# tvc-soundmagic-v1_3.net
KiCad netlist of a schematic drawn in EAGLE
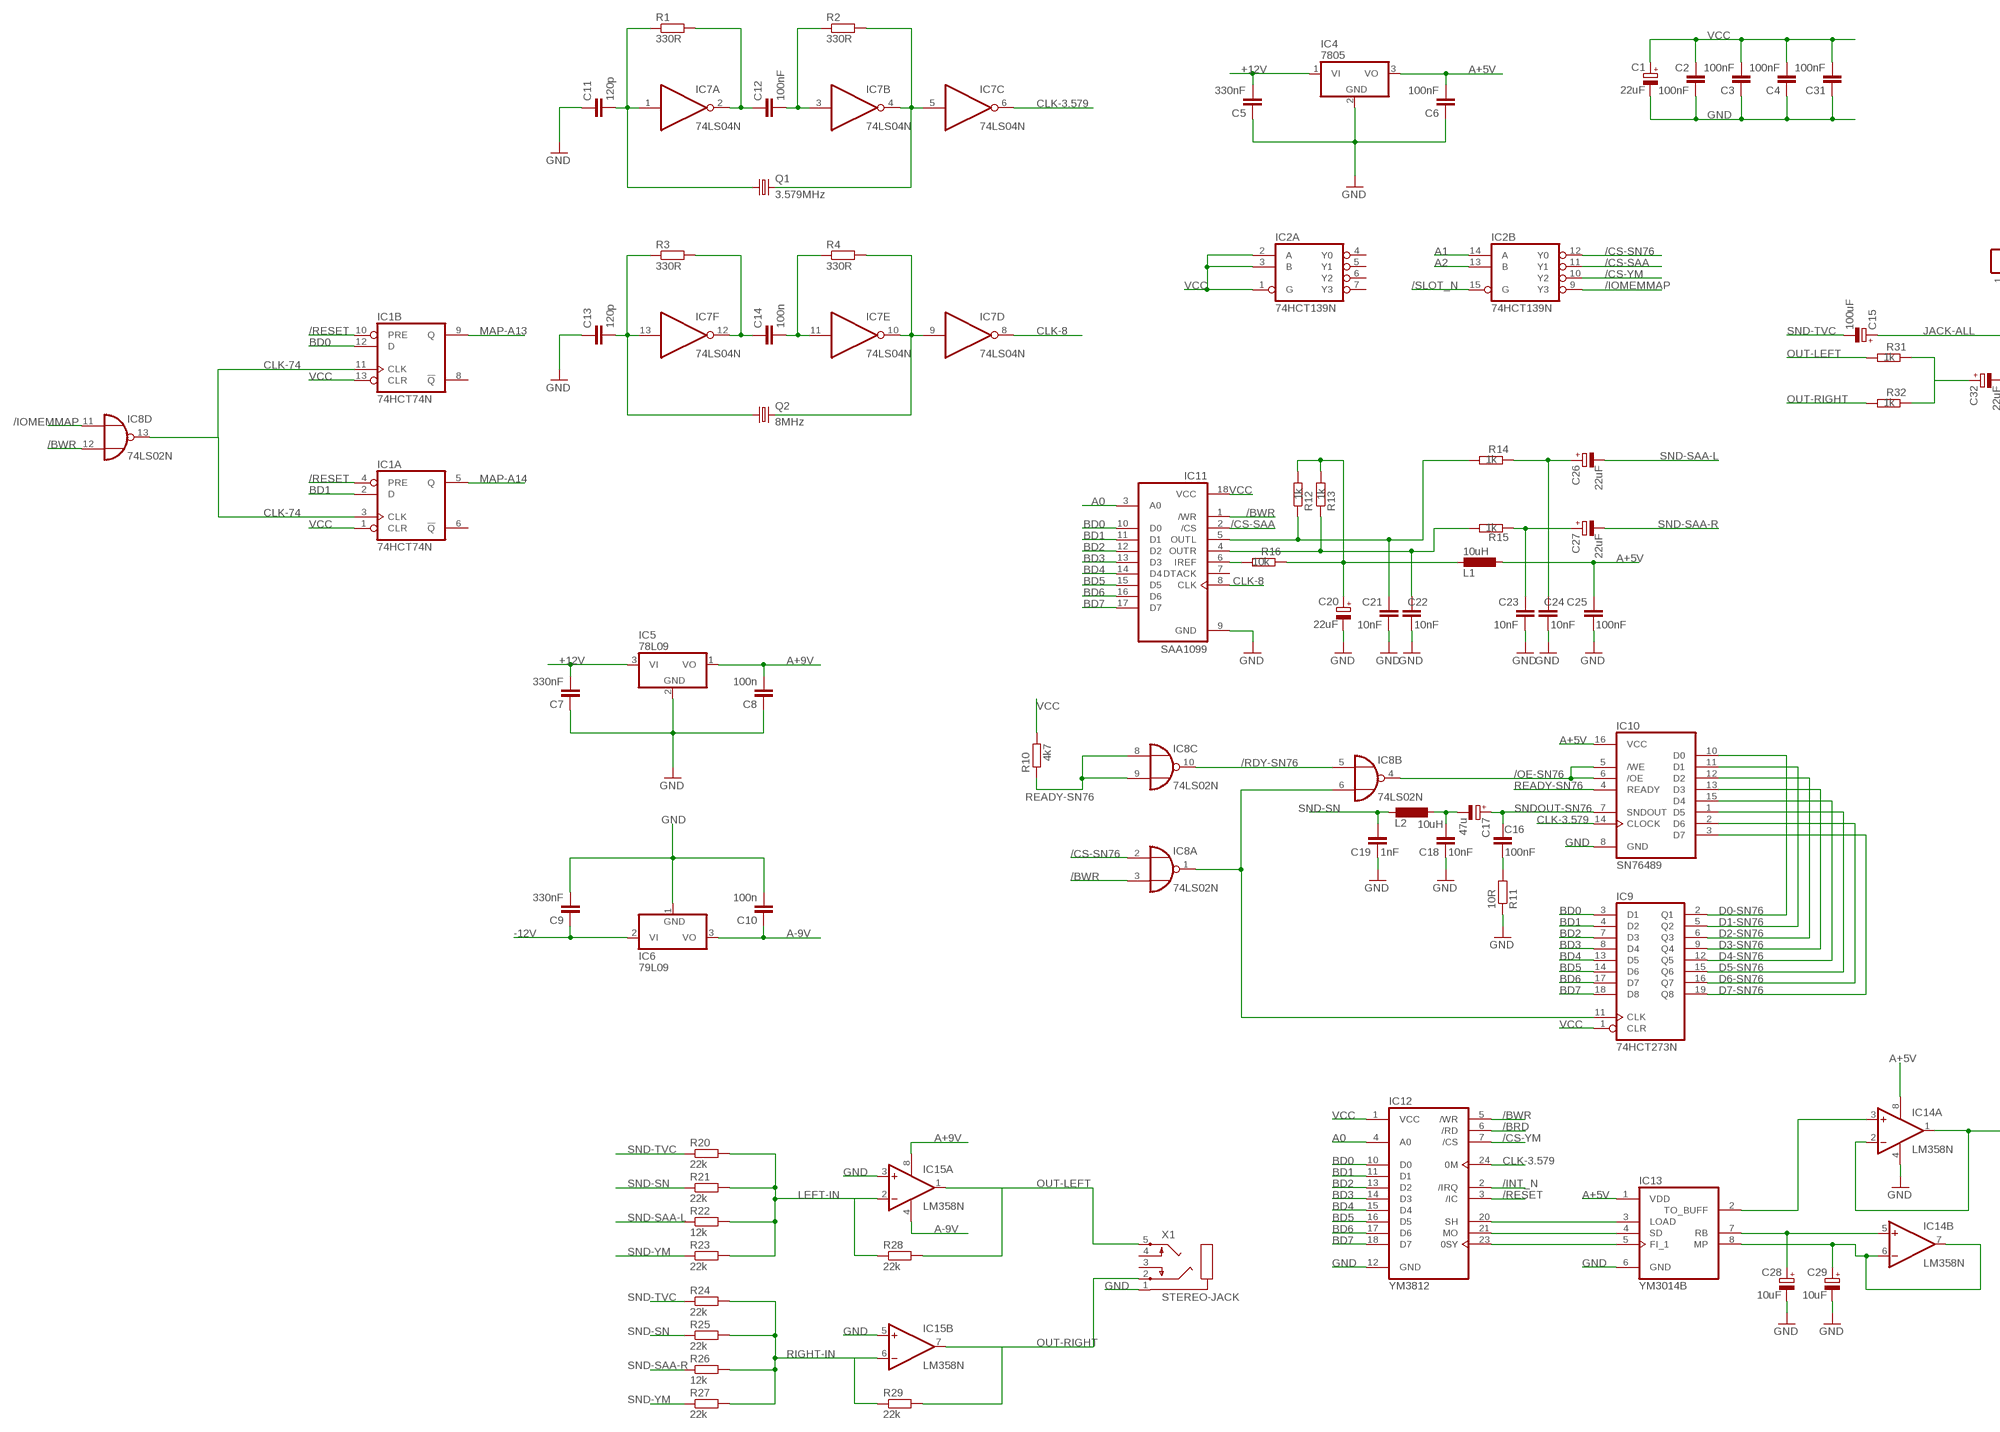
[diagram p0: schematic, sheet 1, part 1 of 2]
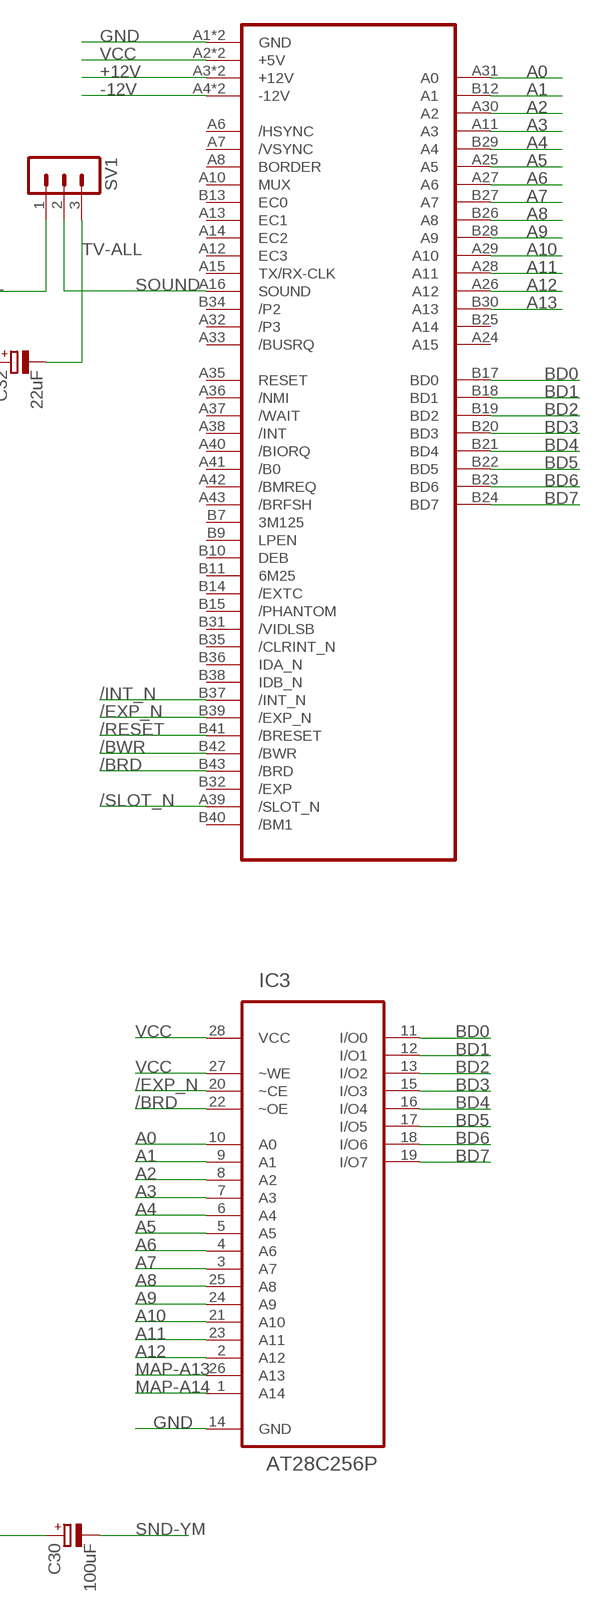
[diagram p1: schematic, sheet 1, part 2 of 2]

(export (version "E")
  (design (tool "Eeschema 10.0.6"))
  (components
    (comp (ref "C1")
      (value "22uF")
      (footprint "eagle-import:E2,5-5")
      (libsource (lib "eagle-import") (part "CPOL-EUE2.5-5"))
    )
    (comp (ref "C2")
      (value "100nF")
      (footprint "eagle-import:C2.5-2")
      (libsource (lib "eagle-import") (part "C2.5/2"))
    )
    (comp (ref "C3")
      (value "100nF")
      (footprint "eagle-import:C025-024X044")
      (libsource (lib "eagle-import") (part "C-EU025-024X044"))
    )
    (comp (ref "C4")
      (value "100nF")
      (footprint "eagle-import:C025-024X044")
      (libsource (lib "eagle-import") (part "C-EU025-024X044"))
    )
    (comp (ref "C5")
      (value "330nF")
      (footprint "eagle-import:C050-025X075")
      (libsource (lib "eagle-import") (part "C-EU050-025X075"))
    )
    (comp (ref "C6")
      (value "100nF")
      (footprint "eagle-import:C025-024X044")
      (libsource (lib "eagle-import") (part "C-EU025-024X044"))
    )
    (comp (ref "C7")
      (value "330nF")
      (footprint "eagle-import:C050-025X075")
      (libsource (lib "eagle-import") (part "C-EU050-025X075"))
    )
    (comp (ref "C8")
      (value "100n")
      (footprint "eagle-import:C025-024X044")
      (libsource (lib "eagle-import") (part "C-EU025-024X044"))
    )
    (comp (ref "C9")
      (value "330nF")
      (footprint "eagle-import:C050-025X075")
      (libsource (lib "eagle-import") (part "C-EU050-025X075"))
    )
    (comp (ref "C10")
      (value "100n")
      (footprint "eagle-import:C025-024X044")
      (libsource (lib "eagle-import") (part "C-EU025-024X044"))
    )
    (comp (ref "C11")
      (value "120p")
      (footprint "eagle-import:C025-024X044")
      (libsource (lib "eagle-import") (part "C-EU025-024X044"))
    )
    (comp (ref "C12")
      (value "100nF")
      (footprint "eagle-import:C025-024X044")
      (libsource (lib "eagle-import") (part "C-EU025-024X044"))
    )
    (comp (ref "C13")
      (value "120p")
      (footprint "eagle-import:C025-024X044")
      (libsource (lib "eagle-import") (part "C-EU025-024X044"))
    )
    (comp (ref "C14")
      (value "100n")
      (footprint "eagle-import:C025-024X044")
      (libsource (lib "eagle-import") (part "C-EU025-024X044"))
    )
    (comp (ref "C15")
      (value "100uF")
      (footprint "eagle-import:E2,5-5")
      (libsource (lib "eagle-import") (part "CPOL-EUE2.5-5"))
    )
    (comp (ref "C16")
      (value "100nF")
      (footprint "eagle-import:C2.5-2")
      (libsource (lib "eagle-import") (part "C2.5/2"))
    )
    (comp (ref "C17")
      (value "47u")
      (footprint "eagle-import:E2,5-6")
      (libsource (lib "eagle-import") (part "resistor_348_CPOL-EUE2.5-6"))
    )
    (comp (ref "C18")
      (value "10nF")
      (footprint "eagle-import:C2.5-2")
      (libsource (lib "eagle-import") (part "C2.5/2"))
    )
    (comp (ref "C19")
      (value "1nF")
      (footprint "eagle-import:C2.5-2")
      (libsource (lib "eagle-import") (part "C2.5/2"))
    )
    (comp (ref "C20")
      (value "22uF")
      (footprint "eagle-import:E2,5-5")
      (libsource (lib "eagle-import") (part "CPOL-EUE2.5-5"))
    )
    (comp (ref "C21")
      (value "10nF")
      (footprint "eagle-import:C2.5-2")
      (libsource (lib "eagle-import") (part "C2.5/2"))
    )
    (comp (ref "C22")
      (value "10nF")
      (footprint "eagle-import:C2.5-2")
      (libsource (lib "eagle-import") (part "C2.5/2"))
    )
    (comp (ref "C23")
      (value "10nF")
      (footprint "eagle-import:C2.5-2")
      (libsource (lib "eagle-import") (part "C2.5/2"))
    )
    (comp (ref "C24")
      (value "10nF")
      (footprint "eagle-import:C2.5-2")
      (libsource (lib "eagle-import") (part "C2.5/2"))
    )
    (comp (ref "C25")
      (value "100nF")
      (footprint "eagle-import:C2.5-2")
      (libsource (lib "eagle-import") (part "C2.5/2"))
    )
    (comp (ref "C26")
      (value "22uF")
      (footprint "eagle-import:E2,5-5")
      (libsource (lib "eagle-import") (part "CPOL-EUE2.5-5"))
    )
    (comp (ref "C27")
      (value "22uF")
      (footprint "eagle-import:E2,5-5")
      (libsource (lib "eagle-import") (part "CPOL-EUE2.5-5"))
    )
    (comp (ref "C28")
      (value "10uF")
      (footprint "eagle-import:E2,5-5")
      (libsource (lib "eagle-import") (part "CPOL-EUE2.5-5"))
    )
    (comp (ref "C29")
      (value "10uF")
      (footprint "eagle-import:E2,5-5")
      (libsource (lib "eagle-import") (part "CPOL-EUE2.5-5"))
    )
    (comp (ref "C30")
      (value "100uF")
      (footprint "eagle-import:E2,5-5")
      (libsource (lib "eagle-import") (part "CPOL-EUE2.5-5"))
    )
    (comp (ref "C31")
      (value "100nF")
      (footprint "eagle-import:C025-024X044")
      (libsource (lib "eagle-import") (part "C-EU025-024X044"))
    )
    (comp (ref "C32")
      (value "22uF")
      (footprint "eagle-import:E2,5-5")
      (libsource (lib "eagle-import") (part "CPOL-EUE2.5-5"))
    )
    (comp (ref "IC1")
      (value "74HCT74N")
      (footprint "eagle-import:DIL14")
      (libsource (lib "eagle-import") (part "7474NHCT"))
    )
    (comp (ref "IC2")
      (value "74HCT139N")
      (footprint "eagle-import:DIL16")
      (libsource (lib "eagle-import") (part "74139NHCT"))
    )
    (comp (ref "IC3")
      (value "AT28C256P")
      (footprint "eagle-import:DIL28-6")
      (libsource (lib "eagle-import") (part "AT28C256P"))
    )
    (comp (ref "IC4")
      (value "7805")
      (footprint "eagle-import:TO220H")
      (libsource (lib "eagle-import") (part "78T05"))
    )
    (comp (ref "IC5")
      (value "78L09")
      (footprint "eagle-import:TO92")
      (libsource (lib "eagle-import") (part "78L09"))
    )
    (comp (ref "IC6")
      (value "79L09")
      (footprint "eagle-import:TO92")
      (libsource (lib "eagle-import") (part "79L09"))
    )
    (comp (ref "IC7")
      (value "74LS04N")
      (footprint "eagle-import:DIL14")
      (libsource (lib "eagle-import") (part "7404NLS"))
    )
    (comp (ref "IC8")
      (value "74LS02N")
      (footprint "eagle-import:DIL14")
      (libsource (lib "eagle-import") (part "7402NLS"))
    )
    (comp (ref "IC9")
      (value "74HCT273N")
      (footprint "eagle-import:DIL20")
      (libsource (lib "eagle-import") (part "74273NHCT"))
    )
    (comp (ref "IC10")
      (value "SN76489")
      (footprint "eagle-import:DIL16")
      (libsource (lib "eagle-import") (part "SN76489"))
    )
    (comp (ref "IC11")
      (value "SAA1099")
      (footprint "eagle-import:DIL18")
      (libsource (lib "eagle-import") (part "SAA1099"))
    )
    (comp (ref "IC12")
      (value "YM3812")
      (footprint "eagle-import:DIL24-6")
      (libsource (lib "eagle-import") (part "YM3812"))
    )
    (comp (ref "IC13")
      (value "YM3014B")
      (footprint "eagle-import:DIL08")
      (libsource (lib "eagle-import") (part "YM3014B"))
    )
    (comp (ref "IC14")
      (value "LM358N")
      (footprint "eagle-import:DIL08")
      (libsource (lib "eagle-import") (part "LM358N"))
    )
    (comp (ref "IC15")
      (value "LM358N")
      (footprint "eagle-import:DIL08")
      (libsource (lib "eagle-import") (part "LM358N"))
    )
    (comp (ref "L1")
      (value "10uH")
      (footprint "eagle-import:0207_10")
      (libsource (lib "eagle-import") (part "L-EU0207/10"))
    )
    (comp (ref "L2")
      (value "10uH")
      (footprint "eagle-import:0207_10")
      (libsource (lib "eagle-import") (part "L-EU0207/10"))
    )
    (comp (ref "Q1")
      (value "3.579MHz")
      (footprint "eagle-import:HC49_S")
      (libsource (lib "eagle-import") (part "CRYSTALHC49S"))
    )
    (comp (ref "Q2")
      (value "8MHz")
      (footprint "eagle-import:HC49_S")
      (libsource (lib "eagle-import") (part "CRYSTALHC49S"))
    )
    (comp (ref "R1")
      (value "330R")
      (footprint "eagle-import:0204_5")
      (libsource (lib "eagle-import") (part "R-EU_0204/5"))
    )
    (comp (ref "R2")
      (value "330R")
      (footprint "eagle-import:0204_5")
      (libsource (lib "eagle-import") (part "R-EU_0204/5"))
    )
    (comp (ref "R3")
      (value "330R")
      (footprint "eagle-import:0204_5")
      (libsource (lib "eagle-import") (part "R-EU_0204/5"))
    )
    (comp (ref "R4")
      (value "330R")
      (footprint "eagle-import:0204_5")
      (libsource (lib "eagle-import") (part "R-EU_0204/5"))
    )
    (comp (ref "R10")
      (value "4k7")
      (footprint "eagle-import:0207_7")
      (libsource (lib "eagle-import") (part "R-EU_0207/7"))
    )
    (comp (ref "R11")
      (value "10R")
      (footprint "eagle-import:0207_7")
      (libsource (lib "eagle-import") (part "R-EU_0207/7"))
    )
    (comp (ref "R12")
      (value "1k")
      (footprint "eagle-import:0207_7")
      (libsource (lib "eagle-import") (part "R-EU_0207/7"))
    )
    (comp (ref "R13")
      (value "1k")
      (footprint "eagle-import:0207_7")
      (libsource (lib "eagle-import") (part "R-EU_0207/7"))
    )
    (comp (ref "R14")
      (value "1k")
      (footprint "eagle-import:0207_7")
      (libsource (lib "eagle-import") (part "R-EU_0207/7"))
    )
    (comp (ref "R15")
      (value "1k")
      (footprint "eagle-import:0207_7")
      (libsource (lib "eagle-import") (part "R-EU_0207/7"))
    )
    (comp (ref "R16")
      (value "10k")
      (footprint "eagle-import:0207_7")
      (libsource (lib "eagle-import") (part "R-EU_0207/7"))
    )
    (comp (ref "R20")
      (value "22k")
      (footprint "eagle-import:0204_5")
      (libsource (lib "eagle-import") (part "R-EU_0204/5"))
    )
    (comp (ref "R21")
      (value "22k")
      (footprint "eagle-import:0204_5")
      (libsource (lib "eagle-import") (part "R-EU_0204/5"))
    )
    (comp (ref "R22")
      (value "12k")
      (footprint "eagle-import:0204_5")
      (libsource (lib "eagle-import") (part "R-EU_0204/5"))
    )
    (comp (ref "R23")
      (value "22k")
      (footprint "eagle-import:0204_5")
      (libsource (lib "eagle-import") (part "R-EU_0204/5"))
    )
    (comp (ref "R24")
      (value "22k")
      (footprint "eagle-import:0204_5")
      (libsource (lib "eagle-import") (part "R-EU_0204/5"))
    )
    (comp (ref "R25")
      (value "22k")
      (footprint "eagle-import:0204_5")
      (libsource (lib "eagle-import") (part "R-EU_0204/5"))
    )
    (comp (ref "R26")
      (value "12k")
      (footprint "eagle-import:0204_5")
      (libsource (lib "eagle-import") (part "R-EU_0204/5"))
    )
    (comp (ref "R27")
      (value "22k")
      (footprint "eagle-import:0204_5")
      (libsource (lib "eagle-import") (part "R-EU_0204/5"))
    )
    (comp (ref "R28")
      (value "22k")
      (footprint "eagle-import:0204_5")
      (libsource (lib "eagle-import") (part "R-EU_0204/5"))
    )
    (comp (ref "R29")
      (value "22k")
      (footprint "eagle-import:0204_5")
      (libsource (lib "eagle-import") (part "R-EU_0204/5"))
    )
    (comp (ref "R31")
      (value "1k")
      (footprint "eagle-import:0207_7")
      (libsource (lib "eagle-import") (part "R-EU_0207/7"))
    )
    (comp (ref "R32")
      (value "1k")
      (footprint "eagle-import:0207_7")
      (libsource (lib "eagle-import") (part "R-EU_0207/7"))
    )
    (comp (ref "SV1")
      (value "MA03-1")
      (footprint "eagle-import:MA03-1")
      (libsource (lib "eagle-import") (part "MA03-1"))
    )
    (comp (ref "U$3")
      (value "TVC-EXP-HBA-COMMON")
      (footprint "eagle-import:TVC-EXP-EDGE")
      (libsource (lib "eagle-import") (part "TVC-EXP-HBA-COMMON"))
    )
    (comp (ref "X1")
      (value "STEREO-JACK")
      (footprint "eagle-import:ST-JACK-100")
      (libsource (lib "eagle-import") (part "STEREO-JACK"))
    )
  )
  (nets
    (net (code "1") (name "/+12V") (class "Default")
      (node (ref "C5") (pin "2") (pinfunction "2_2") (pintype "passive"))
      (node (ref "C7") (pin "2") (pinfunction "2_2") (pintype "passive"))
      (node (ref "IC4") (pin "1") (pinfunction "VI_1") (pintype "input"))
      (node (ref "IC5") (pin "3") (pinfunction "VI_3") (pintype "input"))
      (node (ref "U$3") (pin "A3") (pinfunction "+12V_A3") (pintype "power_in"))
      (node (ref "U$3") (pin "B3") (pinfunction "+12V_B3") (pintype "power_in"))
    )
    (net (code "2") (name "/-12V") (class "Default")
      (node (ref "C9") (pin "1") (pinfunction "1_1") (pintype "passive"))
      (node (ref "IC6") (pin "2") (pinfunction "VI_2") (pintype "input"))
      (node (ref "U$3") (pin "A4") (pinfunction "-12V_A4") (pintype "power_in"))
      (node (ref "U$3") (pin "B4") (pinfunction "-12V_B4") (pintype "power_in"))
    )
    (net (code "3") (name "/A+5V") (class "Default")
      (node (ref "C25") (pin "1") (pinfunction "1_1") (pintype "passive"))
      (node (ref "C6") (pin "2") (pinfunction "2_2") (pintype "passive"))
      (node (ref "IC10") (pin "16") (pinfunction "VCC_16") (pintype "power_in"))
      (node (ref "IC13") (pin "1") (pinfunction "VDD_1") (pintype "power_in"))
      (node (ref "IC14") (pin "8") (pinfunction "V+_8") (pintype "power_in"))
      (node (ref "IC4") (pin "3") (pinfunction "VO_3") (pintype "passive"))
      (node (ref "L1") (pin "1") (pinfunction "1_1") (pintype "passive"))
    )
    (net (code "4") (name "/A+9V") (class "Default")
      (node (ref "C8") (pin "2") (pinfunction "2_2") (pintype "passive"))
      (node (ref "IC15") (pin "8") (pinfunction "V+_8") (pintype "power_in"))
      (node (ref "IC5") (pin "1") (pinfunction "VO_1") (pintype "passive"))
    )
    (net (code "5") (name "/A-9V") (class "Default")
      (node (ref "C10") (pin "1") (pinfunction "1_1") (pintype "passive"))
      (node (ref "IC15") (pin "4") (pinfunction "V-_4") (pintype "power_in"))
      (node (ref "IC6") (pin "3") (pinfunction "VO_3") (pintype "passive"))
    )
    (net (code "6") (name "/A0") (class "Default")
      (node (ref "IC11") (pin "3") (pinfunction "A0_3") (pintype "input"))
      (node (ref "IC12") (pin "4") (pinfunction "A0_4") (pintype "input"))
      (node (ref "IC3") (pin "10") (pinfunction "A0_10") (pintype "input"))
      (node (ref "U$3") (pin "A31") (pinfunction "A0_A31") (pintype "bidirectional"))
    )
    (net (code "7") (name "/A1") (class "Default")
      (node (ref "IC2") (pin "14") (pinfunction "A_14") (pintype "input"))
      (node (ref "IC3") (pin "9") (pinfunction "A1_9") (pintype "input"))
      (node (ref "U$3") (pin "B12") (pinfunction "A1_B12") (pintype "bidirectional"))
    )
    (net (code "8") (name "/A2") (class "Default")
      (node (ref "IC2") (pin "13") (pinfunction "B_13") (pintype "input"))
      (node (ref "IC3") (pin "8") (pinfunction "A2_8") (pintype "input"))
      (node (ref "U$3") (pin "A30") (pinfunction "A2_A30") (pintype "bidirectional"))
    )
    (net (code "9") (name "/A3") (class "Default")
      (node (ref "IC3") (pin "7") (pinfunction "A3_7") (pintype "input"))
      (node (ref "U$3") (pin "A11") (pinfunction "A3_A11") (pintype "bidirectional"))
    )
    (net (code "10") (name "/A4") (class "Default")
      (node (ref "IC3") (pin "6") (pinfunction "A4_6") (pintype "input"))
      (node (ref "U$3") (pin "B29") (pinfunction "A4_B29") (pintype "bidirectional"))
    )
    (net (code "11") (name "/A5") (class "Default")
      (node (ref "IC3") (pin "5") (pinfunction "A5_5") (pintype "input"))
      (node (ref "U$3") (pin "A25") (pinfunction "A5_A25") (pintype "bidirectional"))
    )
    (net (code "12") (name "/A6") (class "Default")
      (node (ref "IC3") (pin "4") (pinfunction "A6_4") (pintype "input"))
      (node (ref "U$3") (pin "A27") (pinfunction "A6_A27") (pintype "bidirectional"))
    )
    (net (code "13") (name "/A7") (class "Default")
      (node (ref "IC3") (pin "3") (pinfunction "A7_3") (pintype "input"))
      (node (ref "U$3") (pin "B27") (pinfunction "A7_B27") (pintype "bidirectional"))
    )
    (net (code "14") (name "/A8") (class "Default")
      (node (ref "IC3") (pin "25") (pinfunction "A8_25") (pintype "input"))
      (node (ref "U$3") (pin "B26") (pinfunction "A8_B26") (pintype "bidirectional"))
    )
    (net (code "15") (name "/A9") (class "Default")
      (node (ref "IC3") (pin "24") (pinfunction "A9_24") (pintype "input"))
      (node (ref "U$3") (pin "B28") (pinfunction "A9_B28") (pintype "bidirectional"))
    )
    (net (code "16") (name "/A10") (class "Default")
      (node (ref "IC3") (pin "21") (pinfunction "A10_21") (pintype "input"))
      (node (ref "U$3") (pin "A29") (pinfunction "A10_A29") (pintype "bidirectional"))
    )
    (net (code "17") (name "/A11") (class "Default")
      (node (ref "IC3") (pin "23") (pinfunction "A11_23") (pintype "input"))
      (node (ref "U$3") (pin "A28") (pinfunction "A11_A28") (pintype "bidirectional"))
    )
    (net (code "18") (name "/A12") (class "Default")
      (node (ref "IC3") (pin "2") (pinfunction "A12_2") (pintype "input"))
      (node (ref "U$3") (pin "A26") (pinfunction "A12_A26") (pintype "bidirectional"))
    )
    (net (code "19") (name "/A13") (class "Default")
      (node (ref "U$3") (pin "B30") (pinfunction "A13_B30") (pintype "bidirectional"))
    )
    (net (code "20") (name "/BD0") (class "Default")
      (node (ref "IC1") (pin "12") (pinfunction "D_12") (pintype "input"))
      (node (ref "IC11") (pin "10") (pinfunction "D0_10") (pintype "bidirectional"))
      (node (ref "IC12") (pin "10") (pinfunction "D0_10") (pintype "bidirectional"))
      (node (ref "IC3") (pin "11") (pinfunction "I/O0_11") (pintype "bidirectional"))
      (node (ref "IC9") (pin "3") (pinfunction "D1_3") (pintype "input"))
      (node (ref "U$3") (pin "B17") (pinfunction "BD0_B17") (pintype "bidirectional"))
    )
    (net (code "21") (name "/BD1") (class "Default")
      (node (ref "IC1") (pin "2") (pinfunction "D_2") (pintype "input"))
      (node (ref "IC11") (pin "11") (pinfunction "D1_11") (pintype "bidirectional"))
      (node (ref "IC12") (pin "11") (pinfunction "D1_11") (pintype "bidirectional"))
      (node (ref "IC3") (pin "12") (pinfunction "I/O1_12") (pintype "bidirectional"))
      (node (ref "IC9") (pin "4") (pinfunction "D2_4") (pintype "input"))
      (node (ref "U$3") (pin "B18") (pinfunction "BD1_B18") (pintype "bidirectional"))
    )
    (net (code "22") (name "/BD2") (class "Default")
      (node (ref "IC11") (pin "12") (pinfunction "D2_12") (pintype "bidirectional"))
      (node (ref "IC12") (pin "13") (pinfunction "D2_13") (pintype "bidirectional"))
      (node (ref "IC3") (pin "13") (pinfunction "I/O2_13") (pintype "bidirectional"))
      (node (ref "IC9") (pin "7") (pinfunction "D3_7") (pintype "input"))
      (node (ref "U$3") (pin "B19") (pinfunction "BD2_B19") (pintype "bidirectional"))
    )
    (net (code "23") (name "/BD3") (class "Default")
      (node (ref "IC11") (pin "13") (pinfunction "D3_13") (pintype "bidirectional"))
      (node (ref "IC12") (pin "14") (pinfunction "D3_14") (pintype "bidirectional"))
      (node (ref "IC3") (pin "15") (pinfunction "I/O3_15") (pintype "bidirectional"))
      (node (ref "IC9") (pin "8") (pinfunction "D4_8") (pintype "input"))
      (node (ref "U$3") (pin "B20") (pinfunction "BD3_B20") (pintype "bidirectional"))
    )
    (net (code "24") (name "/BD4") (class "Default")
      (node (ref "IC11") (pin "14") (pinfunction "D4_14") (pintype "bidirectional"))
      (node (ref "IC12") (pin "15") (pinfunction "D4_15") (pintype "bidirectional"))
      (node (ref "IC3") (pin "16") (pinfunction "I/O4_16") (pintype "bidirectional"))
      (node (ref "IC9") (pin "13") (pinfunction "D5_13") (pintype "input"))
      (node (ref "U$3") (pin "B21") (pinfunction "BD4_B21") (pintype "bidirectional"))
    )
    (net (code "25") (name "/BD5") (class "Default")
      (node (ref "IC11") (pin "15") (pinfunction "D5_15") (pintype "bidirectional"))
      (node (ref "IC12") (pin "16") (pinfunction "D5_16") (pintype "bidirectional"))
      (node (ref "IC3") (pin "17") (pinfunction "I/O5_17") (pintype "bidirectional"))
      (node (ref "IC9") (pin "14") (pinfunction "D6_14") (pintype "input"))
      (node (ref "U$3") (pin "B22") (pinfunction "BD5_B22") (pintype "bidirectional"))
    )
    (net (code "26") (name "/BD6") (class "Default")
      (node (ref "IC11") (pin "16") (pinfunction "D6_16") (pintype "bidirectional"))
      (node (ref "IC12") (pin "17") (pinfunction "D6_17") (pintype "bidirectional"))
      (node (ref "IC3") (pin "18") (pinfunction "I/O6_18") (pintype "bidirectional"))
      (node (ref "IC9") (pin "17") (pinfunction "D7_17") (pintype "input"))
      (node (ref "U$3") (pin "B23") (pinfunction "BD6_B23") (pintype "bidirectional"))
    )
    (net (code "27") (name "/BD7") (class "Default")
      (node (ref "IC11") (pin "17") (pinfunction "D7_17") (pintype "bidirectional"))
      (node (ref "IC12") (pin "18") (pinfunction "D7_18") (pintype "bidirectional"))
      (node (ref "IC3") (pin "19") (pinfunction "I/O7_19") (pintype "bidirectional"))
      (node (ref "IC9") (pin "18") (pinfunction "D8_18") (pintype "input"))
      (node (ref "U$3") (pin "B24") (pinfunction "BD7_B24") (pintype "bidirectional"))
    )
    (net (code "28") (name "/CLK-3.579") (class "Default")
      (node (ref "IC10") (pin "14") (pinfunction "CLOCK_14") (pintype "input"))
      (node (ref "IC12") (pin "24") (pinfunction "0M_24") (pintype "input"))
      (node (ref "IC7") (pin "6") (pinfunction "O_6") (pintype "output"))
    )
    (net (code "29") (name "/CLK-8") (class "Default")
      (node (ref "IC11") (pin "8") (pinfunction "CLK_8") (pintype "input"))
      (node (ref "IC7") (pin "8") (pinfunction "O_8") (pintype "output"))
    )
    (net (code "30") (name "/CLK-74") (class "Default")
      (node (ref "IC1") (pin "11") (pinfunction "CLK_11") (pintype "input"))
      (node (ref "IC1") (pin "3") (pinfunction "CLK_3") (pintype "input"))
      (node (ref "IC8") (pin "13") (pinfunction "O_13") (pintype "output"))
    )
    (net (code "31") (name "/D0-SN76") (class "Default")
      (node (ref "IC10") (pin "10") (pinfunction "D0_10") (pintype "input"))
      (node (ref "IC9") (pin "2") (pinfunction "Q1_2") (pintype "output"))
    )
    (net (code "32") (name "/D1-SN76") (class "Default")
      (node (ref "IC10") (pin "11") (pinfunction "D1_11") (pintype "input"))
      (node (ref "IC9") (pin "5") (pinfunction "Q2_5") (pintype "output"))
    )
    (net (code "33") (name "/D2-SN76") (class "Default")
      (node (ref "IC10") (pin "12") (pinfunction "D2_12") (pintype "input"))
      (node (ref "IC9") (pin "6") (pinfunction "Q3_6") (pintype "output"))
    )
    (net (code "34") (name "/D3-SN76") (class "Default")
      (node (ref "IC10") (pin "13") (pinfunction "D3_13") (pintype "input"))
      (node (ref "IC9") (pin "9") (pinfunction "Q4_9") (pintype "output"))
    )
    (net (code "35") (name "/D4-SN76") (class "Default")
      (node (ref "IC10") (pin "15") (pinfunction "D4_15") (pintype "input"))
      (node (ref "IC9") (pin "12") (pinfunction "Q5_12") (pintype "output"))
    )
    (net (code "36") (name "/D5-SN76") (class "Default")
      (node (ref "IC10") (pin "1") (pinfunction "D5_1") (pintype "input"))
      (node (ref "IC9") (pin "15") (pinfunction "Q6_15") (pintype "output"))
    )
    (net (code "37") (name "/D6-SN76") (class "Default")
      (node (ref "IC10") (pin "2") (pinfunction "D6_2") (pintype "input"))
      (node (ref "IC9") (pin "16") (pinfunction "Q7_16") (pintype "output"))
    )
    (net (code "38") (name "/D7-SN76") (class "Default")
      (node (ref "IC10") (pin "3") (pinfunction "D7_3") (pintype "input"))
      (node (ref "IC9") (pin "19") (pinfunction "Q8_19") (pintype "output"))
    )
    (net (code "39") (name "/JACK-ALL") (class "Default")
      (node (ref "C15") (pin "+") (pinfunction "+_+") (pintype "passive"))
      (node (ref "SV1") (pin "1") (pinfunction "1_1") (pintype "passive"))
    )
    (net (code "40") (name "/LEFT-IN") (class "Default")
      (node (ref "IC15") (pin "2") (pinfunction "-IN_2") (pintype "input"))
      (node (ref "R20") (pin "2") (pinfunction "2_2") (pintype "passive"))
      (node (ref "R21") (pin "2") (pinfunction "2_2") (pintype "passive"))
      (node (ref "R22") (pin "2") (pinfunction "2_2") (pintype "passive"))
      (node (ref "R23") (pin "2") (pinfunction "2_2") (pintype "passive"))
      (node (ref "R28") (pin "1") (pinfunction "1_1") (pintype "passive"))
    )
    (net (code "41") (name "/MAP-A13") (class "Default")
      (node (ref "IC1") (pin "9") (pinfunction "Q_9") (pintype "output"))
      (node (ref "IC3") (pin "26") (pinfunction "A13_26") (pintype "input"))
    )
    (net (code "42") (name "/MAP-A14") (class "Default")
      (node (ref "IC1") (pin "5") (pinfunction "Q_5") (pintype "output"))
      (node (ref "IC3") (pin "1") (pinfunction "A14_1") (pintype "input"))
    )
    (net (code "43") (name "/OUT-LEFT") (class "Default")
      (node (ref "IC15") (pin "1") (pinfunction "OUT_1") (pintype "output"))
      (node (ref "R28") (pin "2") (pinfunction "2_2") (pintype "passive"))
      (node (ref "R31") (pin "2") (pinfunction "2_2") (pintype "passive"))
      (node (ref "X1") (pin "5") (pinfunction "LEFT_5") (pintype "passive"))
    )
    (net (code "44") (name "/OUT-RIGHT") (class "Default")
      (node (ref "IC15") (pin "7") (pinfunction "OUT_7") (pintype "output"))
      (node (ref "R29") (pin "2") (pinfunction "2_2") (pintype "passive"))
      (node (ref "R32") (pin "2") (pinfunction "2_2") (pintype "passive"))
      (node (ref "X1") (pin "2") (pinfunction "RIGHT_2") (pintype "passive"))
    )
    (net (code "45") (name "/READY-SN76") (class "Default")
      (node (ref "IC10") (pin "4") (pinfunction "READY_4") (pintype "open_collector"))
      (node (ref "IC8") (pin "8") (pinfunction "I0_8") (pintype "input"))
      (node (ref "IC8") (pin "9") (pinfunction "I1_9") (pintype "input"))
      (node (ref "R10") (pin "1") (pinfunction "1_1") (pintype "passive"))
    )
    (net (code "46") (name "/RIGHT-IN") (class "Default")
      (node (ref "IC15") (pin "6") (pinfunction "-IN_6") (pintype "input"))
      (node (ref "R24") (pin "2") (pinfunction "2_2") (pintype "passive"))
      (node (ref "R25") (pin "2") (pinfunction "2_2") (pintype "passive"))
      (node (ref "R26") (pin "2") (pinfunction "2_2") (pintype "passive"))
      (node (ref "R27") (pin "2") (pinfunction "2_2") (pintype "passive"))
      (node (ref "R29") (pin "1") (pinfunction "1_1") (pintype "passive"))
    )
    (net (code "47") (name "/SND-SAA-L") (class "Default")
      (node (ref "C26") (pin "-") (pinfunction "-_-") (pintype "passive"))
      (node (ref "R22") (pin "1") (pinfunction "1_1") (pintype "passive"))
    )
    (net (code "48") (name "/SND-SAA-R") (class "Default")
      (node (ref "C27") (pin "-") (pinfunction "-_-") (pintype "passive"))
      (node (ref "R26") (pin "1") (pinfunction "1_1") (pintype "passive"))
    )
    (net (code "49") (name "/SND-SN") (class "Default")
      (node (ref "C19") (pin "1") (pinfunction "1_1") (pintype "passive"))
      (node (ref "L2") (pin "2") (pinfunction "2_2") (pintype "passive"))
      (node (ref "R21") (pin "1") (pinfunction "1_1") (pintype "passive"))
      (node (ref "R25") (pin "1") (pinfunction "1_1") (pintype "passive"))
    )
    (net (code "50") (name "/SND-TVC") (class "Default")
      (node (ref "C15") (pin "-") (pinfunction "-_-") (pintype "passive"))
      (node (ref "R20") (pin "1") (pinfunction "1_1") (pintype "passive"))
      (node (ref "R24") (pin "1") (pinfunction "1_1") (pintype "passive"))
    )
    (net (code "51") (name "/SND-YM") (class "Default")
      (node (ref "C30") (pin "-") (pinfunction "-_-") (pintype "passive"))
      (node (ref "R23") (pin "1") (pinfunction "1_1") (pintype "passive"))
      (node (ref "R27") (pin "1") (pinfunction "1_1") (pintype "passive"))
    )
    (net (code "52") (name "/SNDOUT-SN76") (class "Default")
      (node (ref "C16") (pin "1") (pinfunction "1_1") (pintype "passive"))
      (node (ref "C17") (pin "+") (pinfunction "+_+") (pintype "passive"))
      (node (ref "IC10") (pin "7") (pinfunction "SNDOUT_7") (pintype "open_collector"))
    )
    (net (code "53") (name "/SOUND") (class "Default")
      (node (ref "SV1") (pin "2") (pinfunction "2_2") (pintype "passive"))
      (node (ref "U$3") (pin "A16") (pinfunction "SOUND_A16") (pintype "bidirectional"))
    )
    (net (code "54") (name "/TV-ALL") (class "Default")
      (node (ref "C32") (pin "-") (pinfunction "-_-") (pintype "passive"))
      (node (ref "SV1") (pin "3") (pinfunction "3_3") (pintype "passive"))
    )
    (net (code "55") (name "/VCC") (class "Default")
      (node (ref "C1") (pin "+") (pinfunction "+_+") (pintype "passive"))
      (node (ref "C2") (pin "1") (pinfunction "1_1") (pintype "passive"))
      (node (ref "C3") (pin "2") (pinfunction "2_2") (pintype "passive"))
      (node (ref "C31") (pin "2") (pinfunction "2_2") (pintype "passive"))
      (node (ref "C4") (pin "2") (pinfunction "2_2") (pintype "passive"))
      (node (ref "IC1") (pin "1") (pinfunction "CLR_1") (pintype "input"))
      (node (ref "IC1") (pin "13") (pinfunction "CLR_13") (pintype "input"))
      (node (ref "IC11") (pin "18") (pinfunction "VCC_18") (pintype "power_in"))
      (node (ref "IC12") (pin "1") (pinfunction "VCC_1") (pintype "power_in"))
      (node (ref "IC2") (pin "1") (pinfunction "G_1") (pintype "input"))
      (node (ref "IC2") (pin "2") (pinfunction "A_2") (pintype "input"))
      (node (ref "IC2") (pin "3") (pinfunction "B_3") (pintype "input"))
      (node (ref "IC3") (pin "27") (pinfunction "~{WE}_27") (pintype "input"))
      (node (ref "IC3") (pin "28") (pinfunction "VCC_28") (pintype "power_in"))
      (node (ref "IC9") (pin "1") (pinfunction "CLR_1") (pintype "input"))
      (node (ref "R10") (pin "2") (pinfunction "2_2") (pintype "passive"))
      (node (ref "U$3") (pin "A2") (pinfunction "+5V_A2") (pintype "power_in"))
      (node (ref "U$3") (pin "B2") (pinfunction "+5V_B2") (pintype "power_in"))
    )
    (net (code "56") (name "/{slash}BRD") (class "Default")
      (node (ref "IC12") (pin "6") (pinfunction "/RD_6") (pintype "input"))
      (node (ref "IC3") (pin "22") (pinfunction "~{OE}_22") (pintype "input"))
      (node (ref "U$3") (pin "B43") (pinfunction "/BRD_B43") (pintype "output"))
    )
    (net (code "57") (name "/{slash}BWR") (class "Default")
      (node (ref "IC11") (pin "1") (pinfunction "/WR_1") (pintype "input"))
      (node (ref "IC12") (pin "5") (pinfunction "/WR_5") (pintype "input"))
      (node (ref "IC8") (pin "12") (pinfunction "I1_12") (pintype "input"))
      (node (ref "IC8") (pin "3") (pinfunction "I1_3") (pintype "input"))
      (node (ref "U$3") (pin "B42") (pinfunction "/BWR_B42") (pintype "output"))
    )
    (net (code "58") (name "/{slash}CS-SAA") (class "Default")
      (node (ref "IC11") (pin "2") (pinfunction "/CS_2") (pintype "input"))
      (node (ref "IC2") (pin "11") (pinfunction "Y1_11") (pintype "output"))
    )
    (net (code "59") (name "/{slash}CS-SN76") (class "Default")
      (node (ref "IC2") (pin "12") (pinfunction "Y0_12") (pintype "output"))
      (node (ref "IC8") (pin "2") (pinfunction "I0_2") (pintype "input"))
    )
    (net (code "60") (name "/{slash}CS-YM") (class "Default")
      (node (ref "IC12") (pin "7") (pinfunction "/CS_7") (pintype "output"))
      (node (ref "IC2") (pin "10") (pinfunction "Y2_10") (pintype "output"))
    )
    (net (code "61") (name "/{slash}EXP_N") (class "Default")
      (node (ref "IC3") (pin "20") (pinfunction "~{CE}_20") (pintype "input"))
      (node (ref "U$3") (pin "B39") (pinfunction "/EXP_N_B39") (pintype "bidirectional"))
    )
    (net (code "62") (name "/{slash}INT_N") (class "Default")
      (node (ref "IC12") (pin "2") (pinfunction "/IRQ_2") (pintype "output"))
      (node (ref "U$3") (pin "B37") (pinfunction "/INT_N_B37") (pintype "bidirectional"))
    )
    (net (code "63") (name "/{slash}IOMEMMAP") (class "Default")
      (node (ref "IC2") (pin "9") (pinfunction "Y3_9") (pintype "output"))
      (node (ref "IC8") (pin "11") (pinfunction "I0_11") (pintype "input"))
    )
    (net (code "64") (name "/{slash}OE-SN76") (class "Default")
      (node (ref "IC10") (pin "5") (pinfunction "/WE_5") (pintype "input"))
      (node (ref "IC10") (pin "6") (pinfunction "/OE_6") (pintype "input"))
      (node (ref "IC8") (pin "4") (pinfunction "O_4") (pintype "output"))
    )
    (net (code "65") (name "/{slash}RDY-SN76") (class "Default")
      (node (ref "IC8") (pin "10") (pinfunction "O_10") (pintype "output"))
      (node (ref "IC8") (pin "5") (pinfunction "I0_5") (pintype "input"))
    )
    (net (code "66") (name "/{slash}RESET") (class "Default")
      (node (ref "IC1") (pin "10") (pinfunction "PRE_10") (pintype "input"))
      (node (ref "IC1") (pin "4") (pinfunction "PRE_4") (pintype "input"))
      (node (ref "IC12") (pin "3") (pinfunction "/IC_3") (pintype "input"))
      (node (ref "U$3") (pin "B41") (pinfunction "/BRESET_B41") (pintype "bidirectional"))
    )
    (net (code "67") (name "/{slash}SLOT_N") (class "Default")
      (node (ref "IC2") (pin "15") (pinfunction "G_15") (pintype "input"))
      (node (ref "U$3") (pin "A39") (pinfunction "/SLOT_N_A39") (pintype "input"))
    )
    (net (code "68") (name "GND") (class "Default")
      (node (ref "C1") (pin "-") (pinfunction "-_-") (pintype "passive"))
      (node (ref "C10") (pin "2") (pinfunction "2_2") (pintype "passive"))
      (node (ref "C11") (pin "1") (pinfunction "1_1") (pintype "passive"))
      (node (ref "C13") (pin "1") (pinfunction "1_1") (pintype "passive"))
      (node (ref "C18") (pin "2") (pinfunction "2_2") (pintype "passive"))
      (node (ref "C19") (pin "2") (pinfunction "2_2") (pintype "passive"))
      (node (ref "C2") (pin "2") (pinfunction "2_2") (pintype "passive"))
      (node (ref "C20") (pin "-") (pinfunction "-_-") (pintype "passive"))
      (node (ref "C21") (pin "2") (pinfunction "2_2") (pintype "passive"))
      (node (ref "C22") (pin "2") (pinfunction "2_2") (pintype "passive"))
      (node (ref "C23") (pin "2") (pinfunction "2_2") (pintype "passive"))
      (node (ref "C24") (pin "2") (pinfunction "2_2") (pintype "passive"))
      (node (ref "C25") (pin "2") (pinfunction "2_2") (pintype "passive"))
      (node (ref "C28") (pin "-") (pinfunction "-_-") (pintype "passive"))
      (node (ref "C29") (pin "-") (pinfunction "-_-") (pintype "passive"))
      (node (ref "C3") (pin "1") (pinfunction "1_1") (pintype "passive"))
      (node (ref "C31") (pin "1") (pinfunction "1_1") (pintype "passive"))
      (node (ref "C4") (pin "1") (pinfunction "1_1") (pintype "passive"))
      (node (ref "C5") (pin "1") (pinfunction "1_1") (pintype "passive"))
      (node (ref "C6") (pin "1") (pinfunction "1_1") (pintype "passive"))
      (node (ref "C7") (pin "1") (pinfunction "1_1") (pintype "passive"))
      (node (ref "C8") (pin "1") (pinfunction "1_1") (pintype "passive"))
      (node (ref "C9") (pin "2") (pinfunction "2_2") (pintype "passive"))
      (node (ref "IC10") (pin "8") (pinfunction "GND_8") (pintype "power_in"))
      (node (ref "IC11") (pin "9") (pinfunction "GND_9") (pintype "power_in"))
      (node (ref "IC12") (pin "12") (pinfunction "GND_12") (pintype "power_in"))
      (node (ref "IC13") (pin "6") (pinfunction "GND_6") (pintype "power_in"))
      (node (ref "IC14") (pin "4") (pinfunction "V-_4") (pintype "power_in"))
      (node (ref "IC15") (pin "3") (pinfunction "+IN_3") (pintype "input"))
      (node (ref "IC15") (pin "5") (pinfunction "+IN_5") (pintype "input"))
      (node (ref "IC3") (pin "14") (pinfunction "GND_14") (pintype "passive"))
      (node (ref "IC4") (pin "2") (pinfunction "GND_2") (pintype "passive"))
      (node (ref "IC5") (pin "2") (pinfunction "GND_2") (pintype "passive"))
      (node (ref "IC6") (pin "1") (pinfunction "GND_1") (pintype "passive"))
      (node (ref "R11") (pin "1") (pinfunction "1_1") (pintype "passive"))
      (node (ref "U$3") (pin "A1") (pinfunction "GND_A1") (pintype "power_in"))
      (node (ref "U$3") (pin "B1") (pinfunction "GND_B1") (pintype "power_in"))
      (node (ref "X1") (pin "1") (pinfunction "SHIELD_1") (pintype "passive"))
    )
    (net (code "69") (name "Net-(C16-Pad2)") (class "Default")
      (node (ref "C16") (pin "2") (pinfunction "2_2") (pintype "passive"))
      (node (ref "R11") (pin "2") (pinfunction "2_2") (pintype "passive"))
    )
    (net (code "70") (name "Net-(C17-Pad-)") (class "Default")
      (node (ref "C17") (pin "-") (pinfunction "-_-") (pintype "passive"))
      (node (ref "C18") (pin "1") (pinfunction "1_1") (pintype "passive"))
      (node (ref "L2") (pin "1") (pinfunction "1_1") (pintype "passive"))
    )
    (net (code "71") (name "Net-(C20-Pad+)") (class "Default")
      (node (ref "C20") (pin "+") (pinfunction "+_+") (pintype "passive"))
      (node (ref "L1") (pin "2") (pinfunction "2_2") (pintype "passive"))
      (node (ref "R12") (pin "2") (pinfunction "2_2") (pintype "passive"))
      (node (ref "R13") (pin "2") (pinfunction "2_2") (pintype "passive"))
      (node (ref "R16") (pin "1") (pinfunction "1_1") (pintype "passive"))
    )
    (net (code "72") (name "Net-(C23-Pad1)") (class "Default")
      (node (ref "C23") (pin "1") (pinfunction "1_1") (pintype "passive"))
      (node (ref "C27") (pin "+") (pinfunction "+_+") (pintype "passive"))
      (node (ref "R15") (pin "1") (pinfunction "1_1") (pintype "passive"))
    )
    (net (code "73") (name "Net-(C24-Pad1)") (class "Default")
      (node (ref "C24") (pin "1") (pinfunction "1_1") (pintype "passive"))
      (node (ref "C26") (pin "+") (pinfunction "+_+") (pintype "passive"))
      (node (ref "R14") (pin "1") (pinfunction "1_1") (pintype "passive"))
    )
    (net (code "74") (name "Net-(C32-Pad+)") (class "Default")
      (node (ref "C32") (pin "+") (pinfunction "+_+") (pintype "passive"))
      (node (ref "R31") (pin "1") (pinfunction "1_1") (pintype "passive"))
      (node (ref "R32") (pin "1") (pinfunction "1_1") (pintype "passive"))
    )
    (net (code "75") (name "Net-(IC7A-I)") (class "Default")
      (node (ref "C11") (pin "2") (pinfunction "2_2") (pintype "passive"))
      (node (ref "IC7") (pin "1") (pinfunction "I_1") (pintype "input"))
      (node (ref "Q1") (pin "1") (pinfunction "1_1") (pintype "passive"))
      (node (ref "R1") (pin "1") (pinfunction "1_1") (pintype "passive"))
    )
    (net (code "76") (name "Net-(IC7A-O)") (class "Default")
      (node (ref "C12") (pin "1") (pinfunction "1_1") (pintype "passive"))
      (node (ref "IC7") (pin "2") (pinfunction "O_2") (pintype "output"))
      (node (ref "R1") (pin "2") (pinfunction "2_2") (pintype "passive"))
    )
    (net (code "77") (name "Net-(IC7B-I)") (class "Default")
      (node (ref "C12") (pin "2") (pinfunction "2_2") (pintype "passive"))
      (node (ref "IC7") (pin "3") (pinfunction "I_3") (pintype "input"))
      (node (ref "R2") (pin "1") (pinfunction "1_1") (pintype "passive"))
    )
    (net (code "78") (name "Net-(IC7B-O)") (class "Default")
      (node (ref "IC7") (pin "4") (pinfunction "O_4") (pintype "output"))
      (node (ref "IC7") (pin "5") (pinfunction "I_5") (pintype "input"))
      (node (ref "Q1") (pin "2") (pinfunction "2_2") (pintype "passive"))
      (node (ref "R2") (pin "2") (pinfunction "2_2") (pintype "passive"))
    )
    (net (code "79") (name "Net-(IC7D-I)") (class "Default")
      (node (ref "IC7") (pin "10") (pinfunction "O_10") (pintype "output"))
      (node (ref "IC7") (pin "9") (pinfunction "I_9") (pintype "input"))
      (node (ref "Q2") (pin "2") (pinfunction "2_2") (pintype "passive"))
      (node (ref "R4") (pin "2") (pinfunction "2_2") (pintype "passive"))
    )
    (net (code "80") (name "Net-(IC7E-I)") (class "Default")
      (node (ref "C14") (pin "2") (pinfunction "2_2") (pintype "passive"))
      (node (ref "IC7") (pin "11") (pinfunction "I_11") (pintype "input"))
      (node (ref "R4") (pin "1") (pinfunction "1_1") (pintype "passive"))
    )
    (net (code "81") (name "Net-(IC7F-I)") (class "Default")
      (node (ref "C13") (pin "2") (pinfunction "2_2") (pintype "passive"))
      (node (ref "IC7") (pin "13") (pinfunction "I_13") (pintype "input"))
      (node (ref "Q2") (pin "1") (pinfunction "1_1") (pintype "passive"))
      (node (ref "R3") (pin "1") (pinfunction "1_1") (pintype "passive"))
    )
    (net (code "82") (name "Net-(IC7F-O)") (class "Default")
      (node (ref "C14") (pin "1") (pinfunction "1_1") (pintype "passive"))
      (node (ref "IC7") (pin "12") (pinfunction "O_12") (pintype "output"))
      (node (ref "R3") (pin "2") (pinfunction "2_2") (pintype "passive"))
    )
    (net (code "83") (name "Net-(IC8A-O)") (class "Default")
      (node (ref "IC8") (pin "1") (pinfunction "O_1") (pintype "output"))
      (node (ref "IC8") (pin "6") (pinfunction "I1_6") (pintype "input"))
      (node (ref "IC9") (pin "11") (pinfunction "CLK_11") (pintype "input"))
    )
    (net (code "84") (name "Net-(IC11-IREF)") (class "Default")
      (node (ref "IC11") (pin "6") (pinfunction "IREF_6") (pintype "input"))
      (node (ref "R16") (pin "2") (pinfunction "2_2") (pintype "passive"))
    )
    (net (code "85") (name "Net-(IC11-OUTL)") (class "Default")
      (node (ref "C21") (pin "1") (pinfunction "1_1") (pintype "passive"))
      (node (ref "IC11") (pin "5") (pinfunction "OUTL_5") (pintype "output"))
      (node (ref "R12") (pin "1") (pinfunction "1_1") (pintype "passive"))
      (node (ref "R14") (pin "2") (pinfunction "2_2") (pintype "passive"))
    )
    (net (code "86") (name "Net-(IC11-OUTR)") (class "Default")
      (node (ref "C22") (pin "1") (pinfunction "1_1") (pintype "passive"))
      (node (ref "IC11") (pin "4") (pinfunction "OUTR_4") (pintype "output"))
      (node (ref "R13") (pin "1") (pinfunction "1_1") (pintype "passive"))
      (node (ref "R15") (pin "2") (pinfunction "2_2") (pintype "passive"))
    )
    (net (code "87") (name "Net-(IC12-0SY)") (class "Default")
      (node (ref "IC12") (pin "23") (pinfunction "0SY_23") (pintype "output"))
      (node (ref "IC13") (pin "5") (pinfunction "FI_1_5") (pintype "input"))
    )
    (net (code "88") (name "Net-(IC12-MO)") (class "Default")
      (node (ref "IC12") (pin "21") (pinfunction "MO_21") (pintype "output"))
      (node (ref "IC13") (pin "4") (pinfunction "SD_4") (pintype "bidirectional"))
    )
    (net (code "89") (name "Net-(IC12-SH)") (class "Default")
      (node (ref "IC12") (pin "20") (pinfunction "SH_20") (pintype "output"))
      (node (ref "IC13") (pin "3") (pinfunction "LOAD_3") (pintype "output"))
    )
    (net (code "90") (name "Net-(IC13-MP)") (class "Default")
      (node (ref "C29") (pin "+") (pinfunction "+_+") (pintype "passive"))
      (node (ref "IC13") (pin "8") (pinfunction "MP_8") (pintype "output"))
      (node (ref "IC14") (pin "6") (pinfunction "-IN_6") (pintype "input"))
      (node (ref "IC14") (pin "7") (pinfunction "OUT_7") (pintype "output"))
    )
    (net (code "91") (name "Net-(IC13-RB)") (class "Default")
      (node (ref "C28") (pin "+") (pinfunction "+_+") (pintype "passive"))
      (node (ref "IC13") (pin "7") (pinfunction "RB_7") (pintype "input"))
      (node (ref "IC14") (pin "5") (pinfunction "+IN_5") (pintype "input"))
    )
    (net (code "92") (name "Net-(IC13-TO_BUFF)") (class "Default")
      (node (ref "IC13") (pin "2") (pinfunction "TO_BUFF_2") (pintype "bidirectional"))
      (node (ref "IC14") (pin "3") (pinfunction "+IN_3") (pintype "input"))
    )
    (net (code "93") (name "Net-(IC14A--IN)") (class "Default")
      (node (ref "C30") (pin "+") (pinfunction "+_+") (pintype "passive"))
      (node (ref "IC14") (pin "1") (pinfunction "OUT_1") (pintype "output"))
      (node (ref "IC14") (pin "2") (pinfunction "-IN_2") (pintype "input"))
    )
    (net (code "94") (name "unconnected-(IC1A-~{Q}-Pad6)") (class "Default")
      (node (ref "IC1") (pin "6") (pinfunction "~{Q}_6") (pintype "output"))
    )
    (net (code "95") (name "unconnected-(IC1B-~{Q}-Pad8)") (class "Default")
      (node (ref "IC1") (pin "8") (pinfunction "~{Q}_8") (pintype "output"))
    )
    (net (code "96") (name "unconnected-(IC2A-Y0-Pad4)") (class "Default")
      (node (ref "IC2") (pin "4") (pinfunction "Y0_4") (pintype "output"))
    )
    (net (code "97") (name "unconnected-(IC2A-Y1-Pad5)") (class "Default")
      (node (ref "IC2") (pin "5") (pinfunction "Y1_5") (pintype "output"))
    )
    (net (code "98") (name "unconnected-(IC2A-Y2-Pad6)") (class "Default")
      (node (ref "IC2") (pin "6") (pinfunction "Y2_6") (pintype "output"))
    )
    (net (code "99") (name "unconnected-(IC2A-Y3-Pad7)") (class "Default")
      (node (ref "IC2") (pin "7") (pinfunction "Y3_7") (pintype "output"))
    )
    (net (code "100") (name "unconnected-(IC11-DTACK-Pad7)") (class "Default")
      (node (ref "IC11") (pin "7") (pinfunction "DTACK_7") (pintype "output"))
    )
    (net (code "101") (name "unconnected-(U$3-3M125-PadB7)") (class "Default")
      (node (ref "U$3") (pin "B7") (pinfunction "3M125_B7") (pintype "bidirectional"))
    )
    (net (code "102") (name "unconnected-(U$3-6M25-PadB11)") (class "Default")
      (node (ref "U$3") (pin "B11") (pinfunction "6M25_B11") (pintype "bidirectional"))
    )
    (net (code "103") (name "unconnected-(U$3-A14-PadB25)") (class "Default")
      (node (ref "U$3") (pin "B25") (pinfunction "A14_B25") (pintype "bidirectional"))
    )
    (net (code "104") (name "unconnected-(U$3-A15-PadA24)") (class "Default")
      (node (ref "U$3") (pin "A24") (pinfunction "A15_A24") (pintype "bidirectional"))
    )
    (net (code "105") (name "unconnected-(U$3-BORDER-PadA8)") (class "Default")
      (node (ref "U$3") (pin "A8") (pinfunction "BORDER_A8") (pintype "bidirectional"))
    )
    (net (code "106") (name "unconnected-(U$3-DEB-PadB10)") (class "Default")
      (node (ref "U$3") (pin "B10") (pinfunction "DEB_B10") (pintype "bidirectional"))
    )
    (net (code "107") (name "unconnected-(U$3-EC0-PadB13)") (class "Default")
      (node (ref "U$3") (pin "B13") (pinfunction "EC0_B13") (pintype "bidirectional"))
    )
    (net (code "108") (name "unconnected-(U$3-EC1-PadA13)") (class "Default")
      (node (ref "U$3") (pin "A13") (pinfunction "EC1_A13") (pintype "bidirectional"))
    )
    (net (code "109") (name "unconnected-(U$3-EC2-PadA14)") (class "Default")
      (node (ref "U$3") (pin "A14") (pinfunction "EC2_A14") (pintype "bidirectional"))
    )
    (net (code "110") (name "unconnected-(U$3-EC3-PadA12)") (class "Default")
      (node (ref "U$3") (pin "A12") (pinfunction "EC3_A12") (pintype "bidirectional"))
    )
    (net (code "111") (name "unconnected-(U$3-IDA_N-PadB36)") (class "Default")
      (node (ref "U$3") (pin "B36") (pinfunction "IDA_N_B36") (pintype "bidirectional"))
    )
    (net (code "112") (name "unconnected-(U$3-IDB_N-PadB38)") (class "Default")
      (node (ref "U$3") (pin "B38") (pinfunction "IDB_N_B38") (pintype "bidirectional"))
    )
    (net (code "113") (name "unconnected-(U$3-LPEN-PadB9)") (class "Default")
      (node (ref "U$3") (pin "B9") (pinfunction "LPEN_B9") (pintype "bidirectional"))
    )
    (net (code "114") (name "unconnected-(U$3-MUX-PadA10)") (class "Default")
      (node (ref "U$3") (pin "A10") (pinfunction "MUX_A10") (pintype "bidirectional"))
    )
    (net (code "115") (name "unconnected-(U$3-RESET-PadA35)") (class "Default")
      (node (ref "U$3") (pin "A35") (pinfunction "RESET_A35") (pintype "bidirectional"))
    )
    (net (code "116") (name "unconnected-(U$3-TX{slash}RX-CLK-PadA15)") (class "Default")
      (node (ref "U$3") (pin "A15") (pinfunction "TX/RX-CLK_A15") (pintype "bidirectional"))
    )
    (net (code "117") (name "unconnected-(U$3-{slash}B0-PadA41)") (class "Default")
      (node (ref "U$3") (pin "A41") (pinfunction "/B0_A41") (pintype "bidirectional"))
    )
    (net (code "118") (name "unconnected-(U$3-{slash}BIORQ-PadA40)") (class "Default")
      (node (ref "U$3") (pin "A40") (pinfunction "/BIORQ_A40") (pintype "output"))
    )
    (net (code "119") (name "unconnected-(U$3-{slash}BM1-PadB40)") (class "Default")
      (node (ref "U$3") (pin "B40") (pinfunction "/BM1_B40") (pintype "bidirectional"))
    )
    (net (code "120") (name "unconnected-(U$3-{slash}BMREQ-PadA42)") (class "Default")
      (node (ref "U$3") (pin "A42") (pinfunction "/BMREQ_A42") (pintype "output"))
    )
    (net (code "121") (name "unconnected-(U$3-{slash}BRFSH-PadA43)") (class "Default")
      (node (ref "U$3") (pin "A43") (pinfunction "/BRFSH_A43") (pintype "bidirectional"))
    )
    (net (code "122") (name "unconnected-(U$3-{slash}BUSRQ-PadA33)") (class "Default")
      (node (ref "U$3") (pin "A33") (pinfunction "/BUSRQ_A33") (pintype "bidirectional"))
    )
    (net (code "123") (name "unconnected-(U$3-{slash}CLRINT_N-PadB35)") (class "Default")
      (node (ref "U$3") (pin "B35") (pinfunction "/CLRINT_N_B35") (pintype "bidirectional"))
    )
    (net (code "124") (name "unconnected-(U$3-{slash}EXP-PadB32)") (class "Default")
      (node (ref "U$3") (pin "B32") (pinfunction "/EXP_B32") (pintype "bidirectional"))
    )
    (net (code "125") (name "unconnected-(U$3-{slash}EXTC-PadB14)") (class "Default")
      (node (ref "U$3") (pin "B14") (pinfunction "/EXTC_B14") (pintype "bidirectional"))
    )
    (net (code "126") (name "unconnected-(U$3-{slash}HSYNC-PadA6)") (class "Default")
      (node (ref "U$3") (pin "A6") (pinfunction "/HSYNC_A6") (pintype "bidirectional"))
    )
    (net (code "127") (name "unconnected-(U$3-{slash}INT-PadA38)") (class "Default")
      (node (ref "U$3") (pin "A38") (pinfunction "/INT_A38") (pintype "bidirectional"))
    )
    (net (code "128") (name "unconnected-(U$3-{slash}NMI-PadA36)") (class "Default")
      (node (ref "U$3") (pin "A36") (pinfunction "/NMI_A36") (pintype "bidirectional"))
    )
    (net (code "129") (name "unconnected-(U$3-{slash}P2-PadB34)") (class "Default")
      (node (ref "U$3") (pin "B34") (pinfunction "/P2_B34") (pintype "bidirectional"))
    )
    (net (code "130") (name "unconnected-(U$3-{slash}P3-PadA32)") (class "Default")
      (node (ref "U$3") (pin "A32") (pinfunction "/P3_A32") (pintype "bidirectional"))
    )
    (net (code "131") (name "unconnected-(U$3-{slash}PHANTOM-PadB15)") (class "Default")
      (node (ref "U$3") (pin "B15") (pinfunction "/PHANTOM_B15") (pintype "bidirectional"))
    )
    (net (code "132") (name "unconnected-(U$3-{slash}VIDLSB-PadB31)") (class "Default")
      (node (ref "U$3") (pin "B31") (pinfunction "/VIDLSB_B31") (pintype "bidirectional"))
    )
    (net (code "133") (name "unconnected-(U$3-{slash}VSYNC-PadA7)") (class "Default")
      (node (ref "U$3") (pin "A7") (pinfunction "/VSYNC_A7") (pintype "bidirectional"))
    )
    (net (code "134") (name "unconnected-(U$3-{slash}WAIT-PadA37)") (class "Default")
      (node (ref "U$3") (pin "A37") (pinfunction "/WAIT_A37") (pintype "bidirectional"))
    )
    (net (code "135") (name "unconnected-(X1-L-SWITCH-Pad4)") (class "Default")
      (node (ref "X1") (pin "4") (pinfunction "L-SWITCH_4") (pintype "passive"))
    )
    (net (code "136") (name "unconnected-(X1-R-SWITCH-Pad3)") (class "Default")
      (node (ref "X1") (pin "3") (pinfunction "R-SWITCH_3") (pintype "passive"))
    )
  )
)
